# BNC.net
KiCad netlist of a schematic drawn in Altium Designer
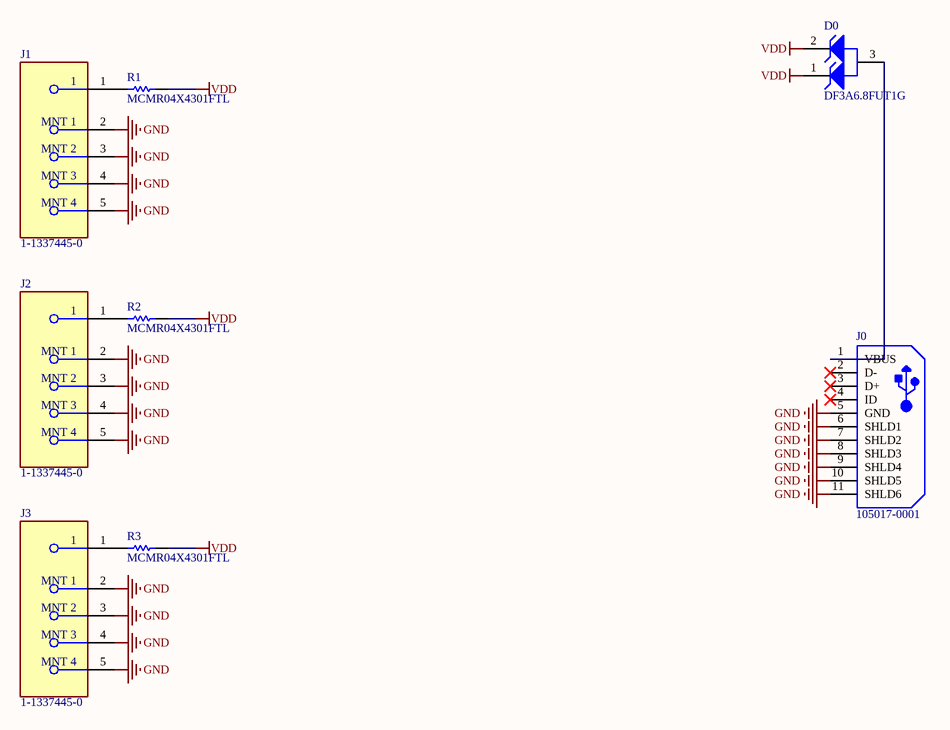
[diagram p0: BNC.SchDoc]

(export (version "E")
  (design (tool "Eeschema 10.0.6"))
  (components
    (comp (ref "D0")
      (value "DF3A6.8FUT1G")
      (footprint "ONSC-SC-70-3-419-04_V")
      (fields (field (name "MANUFACTURER") "On Semiconductor"))
      (libsource (lib "Altium Content Vault") (part "ONSC-K1K2A3-3"))
    )
    (comp (ref "J0")
      (value "105017-0001")
      (footprint "USB-MICRO-B_V")
      (fields (field (name "MANUFACTURER") "Molex"))
      (libsource (lib "Altium Content Vault") (part "USB-5-6SHLD"))
    )
    (comp (ref "J1")
      (value "1-1337445-0")
      (footprint "FP-1-1337445-0-MFG")
      (description "CONN BNC JACK STR 50 OHM PCB")
      (libsource (lib "Altium Content Vault") (part "c65b8a639cdaef1819ea20b5466f8fa"))
    )
    (comp (ref "J2")
      (value "1-1337445-0")
      (footprint "FP-1-1337445-0-MFG")
      (description "CONN BNC JACK STR 50 OHM PCB")
      (libsource (lib "Altium Content Vault") (part "c65b8a639cdaef1819ea20b5466f8fa"))
    )
    (comp (ref "J3")
      (value "1-1337445-0")
      (footprint "FP-1-1337445-0-MFG")
      (description "CONN BNC JACK STR 50 OHM PCB")
      (libsource (lib "Altium Content Vault") (part "c65b8a639cdaef1819ea20b5466f8fa"))
    )
    (comp (ref "R1")
      (value "MCMR04X4301FTL")
      (footprint "RESC1005X40X25LL05T10")
      (fields (field (name "MANUFACTURER") "Multicomp"))
      (libsource (lib "Altium Content Vault") (part "RES"))
    )
    (comp (ref "R2")
      (value "MCMR04X4301FTL")
      (footprint "RESC1005X40X25LL05T10")
      (fields (field (name "MANUFACTURER") "Multicomp"))
      (libsource (lib "Altium Content Vault") (part "RES"))
    )
    (comp (ref "R3")
      (value "MCMR04X4301FTL")
      (footprint "RESC1005X40X25LL05T10")
      (fields (field (name "MANUFACTURER") "Multicomp"))
      (libsource (lib "Altium Content Vault") (part "RES"))
    )
  )
  (nets
    (net (code "1") (name "GND") (class "Default")
      (node (ref "J0") (pin "10") (pinfunction "SHLD5_10") (pintype "passive"))
      (node (ref "J0") (pin "11") (pinfunction "SHLD6_11") (pintype "passive"))
      (node (ref "J0") (pin "5") (pinfunction "GND_5") (pintype "passive"))
      (node (ref "J0") (pin "6") (pinfunction "SHLD1_6") (pintype "passive"))
      (node (ref "J0") (pin "7") (pinfunction "SHLD2_7") (pintype "passive"))
      (node (ref "J0") (pin "8") (pinfunction "SHLD3_8") (pintype "passive"))
      (node (ref "J0") (pin "9") (pinfunction "SHLD4_9") (pintype "passive"))
      (node (ref "J1") (pin "2") (pinfunction "MNT_1_2") (pintype "passive"))
      (node (ref "J1") (pin "3") (pinfunction "MNT_2_3") (pintype "passive"))
      (node (ref "J1") (pin "4") (pinfunction "MNT_3_4") (pintype "passive"))
      (node (ref "J1") (pin "5") (pinfunction "MNT_4_5") (pintype "passive"))
      (node (ref "J2") (pin "2") (pinfunction "MNT_1_2") (pintype "passive"))
      (node (ref "J2") (pin "3") (pinfunction "MNT_2_3") (pintype "passive"))
      (node (ref "J2") (pin "4") (pinfunction "MNT_3_4") (pintype "passive"))
      (node (ref "J2") (pin "5") (pinfunction "MNT_4_5") (pintype "passive"))
      (node (ref "J3") (pin "2") (pinfunction "MNT_1_2") (pintype "passive"))
      (node (ref "J3") (pin "3") (pinfunction "MNT_2_3") (pintype "passive"))
      (node (ref "J3") (pin "4") (pinfunction "MNT_3_4") (pintype "passive"))
      (node (ref "J3") (pin "5") (pinfunction "MNT_4_5") (pintype "passive"))
    )
    (net (code "2") (name "Net-(D0-A)") (class "Default")
      (node (ref "D0") (pin "3") (pinfunction "A_3") (pintype "passive"))
      (node (ref "J0") (pin "1") (pinfunction "VBUS_1") (pintype "passive"))
    )
    (net (code "3") (name "Net-(J1-Pad1)") (class "Default")
      (node (ref "J1") (pin "1") (pinfunction "1_1") (pintype "passive"))
      (node (ref "R1") (pin "1") (pinfunction "1_1") (pintype "passive"))
    )
    (net (code "4") (name "Net-(J2-Pad1)") (class "Default")
      (node (ref "J2") (pin "1") (pinfunction "1_1") (pintype "passive"))
      (node (ref "R2") (pin "1") (pinfunction "1_1") (pintype "passive"))
    )
    (net (code "5") (name "Net-(J3-Pad1)") (class "Default")
      (node (ref "J3") (pin "1") (pinfunction "1_1") (pintype "passive"))
      (node (ref "R3") (pin "1") (pinfunction "1_1") (pintype "passive"))
    )
    (net (code "6") (name "VDD") (class "Default")
      (node (ref "D0") (pin "1") (pinfunction "K1_1") (pintype "passive"))
      (node (ref "D0") (pin "2") (pinfunction "K2_2") (pintype "passive"))
      (node (ref "R1") (pin "2") (pinfunction "2_2") (pintype "passive"))
      (node (ref "R2") (pin "2") (pinfunction "2_2") (pintype "passive"))
      (node (ref "R3") (pin "2") (pinfunction "2_2") (pintype "passive"))
    )
    (net (code "7") (name "unconnected-(J0-D+-Pad3)") (class "Default")
      (node (ref "J0") (pin "3") (pinfunction "D+_3") (pintype "passive+no_connect"))
    )
    (net (code "8") (name "unconnected-(J0-D--Pad2)") (class "Default")
      (node (ref "J0") (pin "2") (pinfunction "D-_2") (pintype "passive+no_connect"))
    )
    (net (code "9") (name "unconnected-(J0-ID-Pad4)") (class "Default")
      (node (ref "J0") (pin "4") (pinfunction "ID_4") (pintype "passive+no_connect"))
    )
  )
)
